# design_EasyDEA.net
KiCad netlist of a schematic drawn in EasyEDA
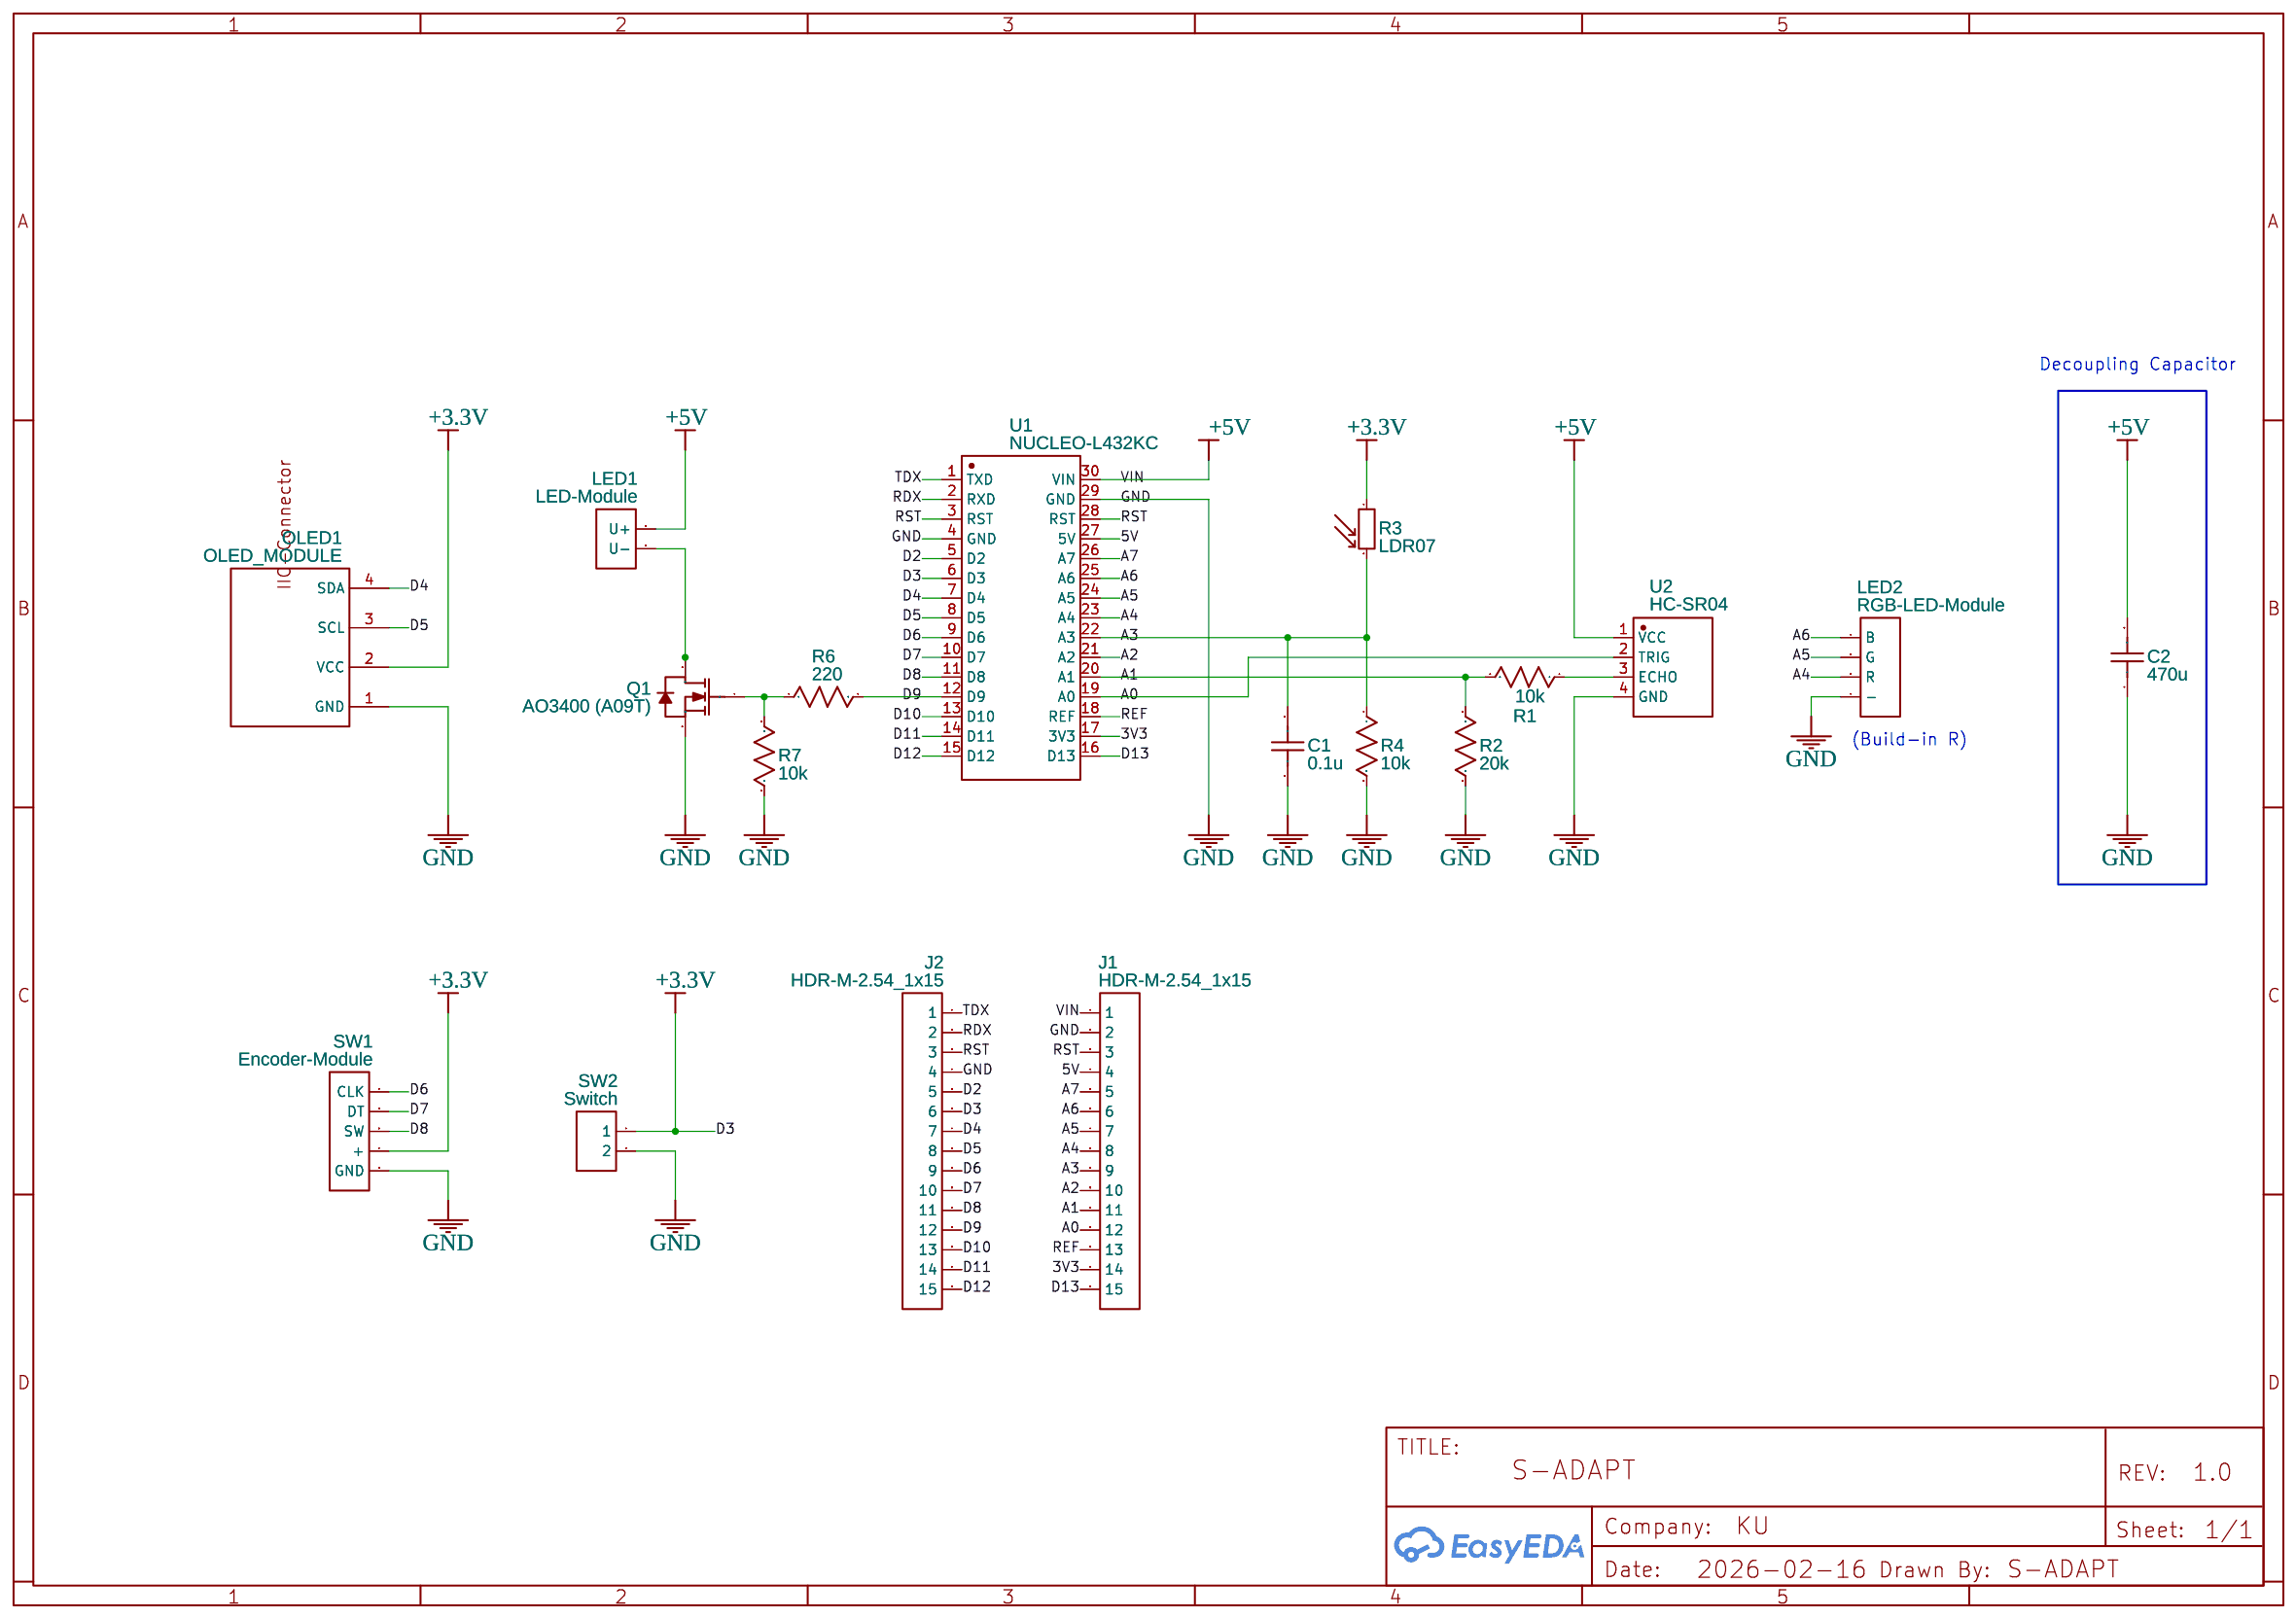
[diagram p0: schematic sheet]

(export (version "E")
  (design (tool "Eeschema 10.0.6"))
  (components
    (comp (ref "C1") (value "0.1u") (libsource (lib "") (part "C_0603_US")))
    (comp (ref "C2") (value "470u") (libsource (lib "") (part "C_0603_US")))
    (comp (ref "J1") (value "HDR-M-2.54_1x15") (libsource (lib "") (part "HDR-M-2.54_1x15")))
    (comp (ref "J2") (value "HDR-M-2.54_1x15") (libsource (lib "") (part "HDR-M-2.54_1x15_1")))
    (comp (ref "LED1") (value "LED-Module") (libsource (lib "") (part "HDR-M-2.54_1x2")))
    (comp (ref "LED2") (value "RGB-LED-Module") (libsource (lib "") (part "HDR-F-2.54_1x4")))
    (comp (ref "OLED1")
      (value "OLED_MODULE")
      (fields (field (name "Manufacturer Part") "0.96OLED_4P_MODULE_JX"))
      (libsource (lib "") (part "0.96OLED_4P_MODULE_JX"))
    )
    (comp (ref "Q1")
      (value "AO3400 (A09T)")
      (fields (field (name "Manufacturer Part") "AO3400NSA") (field (name "Manufacturer") "DOWO(东沃)"))
      (libsource (lib "") (part "AO3400NSA"))
    )
    (comp (ref "R1") (value "10k") (libsource (lib "") (part "R_0603_US")))
    (comp (ref "R2") (value "20k") (libsource (lib "") (part "R_0603_US_1")))
    (comp (ref "R3") (value "LDR07") (libsource (lib "") (part "LDR07")))
    (comp (ref "R4") (value "10k") (libsource (lib "") (part "R_0603_US_2")))
    (comp (ref "R6") (value "220") (libsource (lib "") (part "R_0805_US_1")))
    (comp (ref "R7") (value "10k") (libsource (lib "") (part "R_0805_US")))
    (comp (ref "SW1") (value "Encoder-Module") (libsource (lib "") (part "HDR-F-2.54_1x5")))
    (comp (ref "SW2") (value "Switch") (libsource (lib "") (part "HDR-M-2.54_1x2_1")))
    (comp (ref "U1")
      (value "NUCLEO-L432KC")
      (fields (field (name "Manufacturer") "ST(意法半导体)"))
      (libsource (lib "") (part "NUCLEO-L432KC"))
    )
    (comp (ref "U2")
      (value "HC-SR04")
      (fields (field (name "Manufacturer") "Universal Microelectronics"))
      (libsource (lib "") (part "HC-SR04"))
    )
  )
  (nets
    (net (code "1") (name "+3.3V") (class "Default")
      (node (ref "J2") (pin "6") (pinfunction "6_6") (pintype "unspecified"))
      (node (ref "OLED1") (pin "2") (pinfunction "VCC_2") (pintype "unspecified"))
      (node (ref "R3") (pin "1") (pintype "unspecified"))
      (node (ref "SW1") (pin "4") (pinfunction "+_4") (pintype "unspecified"))
      (node (ref "SW2") (pin "1") (pinfunction "1_1") (pintype "unspecified"))
      (node (ref "U1") (pin "6") (pinfunction "D3_6") (pintype "unspecified"))
    )
    (net (code "2") (name "+5V") (class "Default")
      (node (ref "C2") (pin "2") (pinfunction "2_2") (pintype "unspecified"))
      (node (ref "J1") (pin "1") (pinfunction "1_1") (pintype "unspecified"))
      (node (ref "LED1") (pin "1") (pinfunction "U+_1") (pintype "unspecified"))
      (node (ref "U1") (pin "30") (pinfunction "VIN_30") (pintype "unspecified"))
      (node (ref "U2") (pin "1") (pinfunction "VCC_1") (pintype "unspecified"))
    )
    (net (code "3") (name "/3V3") (class "Default")
      (node (ref "J1") (pin "14") (pinfunction "14_14") (pintype "unspecified"))
      (node (ref "U1") (pin "17") (pinfunction "3V3_17") (pintype "unspecified"))
    )
    (net (code "4") (name "/5V") (class "Default")
      (node (ref "J1") (pin "4") (pinfunction "4_4") (pintype "unspecified"))
      (node (ref "U1") (pin "27") (pinfunction "5V_27") (pintype "unspecified"))
    )
    (net (code "5") (name "/A0") (class "Default")
      (node (ref "J1") (pin "12") (pinfunction "12_12") (pintype "unspecified"))
      (node (ref "U1") (pin "19") (pinfunction "A0_19") (pintype "unspecified"))
      (node (ref "U2") (pin "2") (pinfunction "TRIG_2") (pintype "unspecified"))
    )
    (net (code "6") (name "/A1") (class "Default")
      (node (ref "J1") (pin "11") (pinfunction "11_11") (pintype "unspecified"))
      (node (ref "R1") (pin "2") (pinfunction "2_2") (pintype "unspecified"))
      (node (ref "R2") (pin "2") (pinfunction "2_2") (pintype "unspecified"))
      (node (ref "U1") (pin "20") (pinfunction "A1_20") (pintype "unspecified"))
    )
    (net (code "7") (name "/A2") (class "Default")
      (node (ref "J1") (pin "10") (pinfunction "10_10") (pintype "unspecified"))
      (node (ref "U1") (pin "21") (pinfunction "A2_21") (pintype "unspecified"))
    )
    (net (code "8") (name "/A3") (class "Default")
      (node (ref "C1") (pin "2") (pinfunction "2_2") (pintype "unspecified"))
      (node (ref "J1") (pin "9") (pinfunction "9_9") (pintype "unspecified"))
      (node (ref "R3") (pin "2") (pintype "unspecified"))
      (node (ref "R4") (pin "1") (pinfunction "1_1") (pintype "unspecified"))
      (node (ref "U1") (pin "22") (pinfunction "A3_22") (pintype "unspecified"))
    )
    (net (code "9") (name "/A4") (class "Default")
      (node (ref "J1") (pin "8") (pinfunction "8_8") (pintype "unspecified"))
      (node (ref "LED2") (pin "3") (pinfunction "R_3") (pintype "unspecified"))
      (node (ref "U1") (pin "23") (pinfunction "A4_23") (pintype "unspecified"))
    )
    (net (code "10") (name "/A5") (class "Default")
      (node (ref "J1") (pin "7") (pinfunction "7_7") (pintype "unspecified"))
      (node (ref "LED2") (pin "2") (pinfunction "G_2") (pintype "unspecified"))
      (node (ref "U1") (pin "24") (pinfunction "A5_24") (pintype "unspecified"))
    )
    (net (code "11") (name "/A6") (class "Default")
      (node (ref "J1") (pin "6") (pinfunction "6_6") (pintype "unspecified"))
      (node (ref "LED2") (pin "1") (pinfunction "B_1") (pintype "unspecified"))
      (node (ref "U1") (pin "25") (pinfunction "A6_25") (pintype "unspecified"))
    )
    (net (code "12") (name "/A7") (class "Default")
      (node (ref "J1") (pin "5") (pinfunction "5_5") (pintype "unspecified"))
      (node (ref "U1") (pin "26") (pinfunction "A7_26") (pintype "unspecified"))
    )
    (net (code "13") (name "/D2") (class "Default")
      (node (ref "J2") (pin "5") (pinfunction "5_5") (pintype "unspecified"))
      (node (ref "U1") (pin "5") (pinfunction "D2_5") (pintype "unspecified"))
    )
    (net (code "14") (name "/D4") (class "Default")
      (node (ref "J2") (pin "7") (pinfunction "7_7") (pintype "unspecified"))
      (node (ref "OLED1") (pin "4") (pinfunction "SDA_4") (pintype "unspecified"))
      (node (ref "U1") (pin "7") (pinfunction "D4_7") (pintype "unspecified"))
    )
    (net (code "15") (name "/D5") (class "Default")
      (node (ref "J2") (pin "8") (pinfunction "8_8") (pintype "unspecified"))
      (node (ref "OLED1") (pin "3") (pinfunction "SCL_3") (pintype "unspecified"))
      (node (ref "U1") (pin "8") (pinfunction "D5_8") (pintype "unspecified"))
    )
    (net (code "16") (name "/D6") (class "Default")
      (node (ref "J2") (pin "9") (pinfunction "9_9") (pintype "unspecified"))
      (node (ref "SW1") (pin "1") (pinfunction "CLK_1") (pintype "unspecified"))
      (node (ref "U1") (pin "9") (pinfunction "D6_9") (pintype "unspecified"))
    )
    (net (code "17") (name "/D7") (class "Default")
      (node (ref "J2") (pin "10") (pinfunction "10_10") (pintype "unspecified"))
      (node (ref "SW1") (pin "2") (pinfunction "DT_2") (pintype "unspecified"))
      (node (ref "U1") (pin "10") (pinfunction "D7_10") (pintype "unspecified"))
    )
    (net (code "18") (name "/D8") (class "Default")
      (node (ref "J2") (pin "11") (pinfunction "11_11") (pintype "unspecified"))
      (node (ref "SW1") (pin "3") (pinfunction "SW_3") (pintype "unspecified"))
      (node (ref "U1") (pin "11") (pinfunction "D8_11") (pintype "unspecified"))
    )
    (net (code "19") (name "/D9") (class "Default")
      (node (ref "J2") (pin "12") (pinfunction "12_12") (pintype "unspecified"))
      (node (ref "R6") (pin "2") (pinfunction "2_2") (pintype "unspecified"))
      (node (ref "U1") (pin "12") (pinfunction "D9_12") (pintype "unspecified"))
    )
    (net (code "20") (name "/D10") (class "Default")
      (node (ref "J2") (pin "13") (pinfunction "13_13") (pintype "unspecified"))
      (node (ref "U1") (pin "13") (pinfunction "D10_13") (pintype "unspecified"))
    )
    (net (code "21") (name "/D11") (class "Default")
      (node (ref "J2") (pin "14") (pinfunction "14_14") (pintype "unspecified"))
      (node (ref "U1") (pin "14") (pinfunction "D11_14") (pintype "unspecified"))
    )
    (net (code "22") (name "/D12") (class "Default")
      (node (ref "J2") (pin "15") (pinfunction "15_15") (pintype "unspecified"))
      (node (ref "U1") (pin "15") (pinfunction "D12_15") (pintype "unspecified"))
    )
    (net (code "23") (name "/D13") (class "Default")
      (node (ref "J1") (pin "15") (pinfunction "15_15") (pintype "unspecified"))
      (node (ref "U1") (pin "16") (pinfunction "D13_16") (pintype "unspecified"))
    )
    (net (code "24") (name "/RDX") (class "Default")
      (node (ref "J2") (pin "2") (pinfunction "2_2") (pintype "unspecified"))
      (node (ref "U1") (pin "2") (pinfunction "RXD_2") (pintype "unspecified"))
    )
    (net (code "25") (name "/REF") (class "Default")
      (node (ref "J1") (pin "13") (pinfunction "13_13") (pintype "unspecified"))
      (node (ref "U1") (pin "18") (pinfunction "REF_18") (pintype "unspecified"))
    )
    (net (code "26") (name "/RST") (class "Default")
      (node (ref "J1") (pin "3") (pinfunction "3_3") (pintype "unspecified"))
      (node (ref "J2") (pin "3") (pinfunction "3_3") (pintype "unspecified"))
      (node (ref "U1") (pin "28") (pinfunction "RST_28") (pintype "unspecified"))
      (node (ref "U1") (pin "3") (pinfunction "RST_3") (pintype "unspecified"))
    )
    (net (code "27") (name "/TDX") (class "Default")
      (node (ref "J2") (pin "1") (pinfunction "1_1") (pintype "unspecified"))
      (node (ref "U1") (pin "1") (pinfunction "TXD_1") (pintype "unspecified"))
    )
    (net (code "28") (name "GND") (class "Default")
      (node (ref "C1") (pin "1") (pinfunction "1_1") (pintype "unspecified"))
      (node (ref "C2") (pin "1") (pinfunction "1_1") (pintype "unspecified"))
      (node (ref "J1") (pin "2") (pinfunction "2_2") (pintype "unspecified"))
      (node (ref "J2") (pin "4") (pinfunction "4_4") (pintype "unspecified"))
      (node (ref "LED2") (pin "4") (pinfunction "-_4") (pintype "unspecified"))
      (node (ref "OLED1") (pin "1") (pinfunction "GND_1") (pintype "unspecified"))
      (node (ref "Q1") (pin "2") (pinfunction "S_2") (pintype "unspecified"))
      (node (ref "R2") (pin "1") (pinfunction "1_1") (pintype "unspecified"))
      (node (ref "R4") (pin "2") (pinfunction "2_2") (pintype "unspecified"))
      (node (ref "R7") (pin "1") (pinfunction "1_1") (pintype "unspecified"))
      (node (ref "SW1") (pin "5") (pinfunction "GND_5") (pintype "unspecified"))
      (node (ref "SW2") (pin "2") (pinfunction "2_2") (pintype "unspecified"))
      (node (ref "U1") (pin "29") (pinfunction "GND_29") (pintype "unspecified"))
      (node (ref "U1") (pin "4") (pinfunction "GND_4") (pintype "unspecified"))
      (node (ref "U2") (pin "4") (pinfunction "GND_4") (pintype "unspecified"))
    )
    (net (code "29") (name "Net-(LED1-U-)") (class "Default")
      (node (ref "LED1") (pin "2") (pinfunction "U-_2") (pintype "unspecified"))
      (node (ref "Q1") (pin "3") (pinfunction "D_3") (pintype "unspecified"))
    )
    (net (code "30") (name "Net-(Q1-G)") (class "Default")
      (node (ref "Q1") (pin "1") (pinfunction "G_1") (pintype "unspecified"))
      (node (ref "R6") (pin "1") (pinfunction "1_1") (pintype "unspecified"))
      (node (ref "R7") (pin "2") (pinfunction "2_2") (pintype "unspecified"))
    )
    (net (code "31") (name "Net-(U2-ECHO)") (class "Default")
      (node (ref "R1") (pin "1") (pinfunction "1_1") (pintype "unspecified"))
      (node (ref "U2") (pin "3") (pinfunction "ECHO_3") (pintype "unspecified"))
    )
  )
)
